# v1.net
KiCad netlist of a schematic drawn in EAGLE
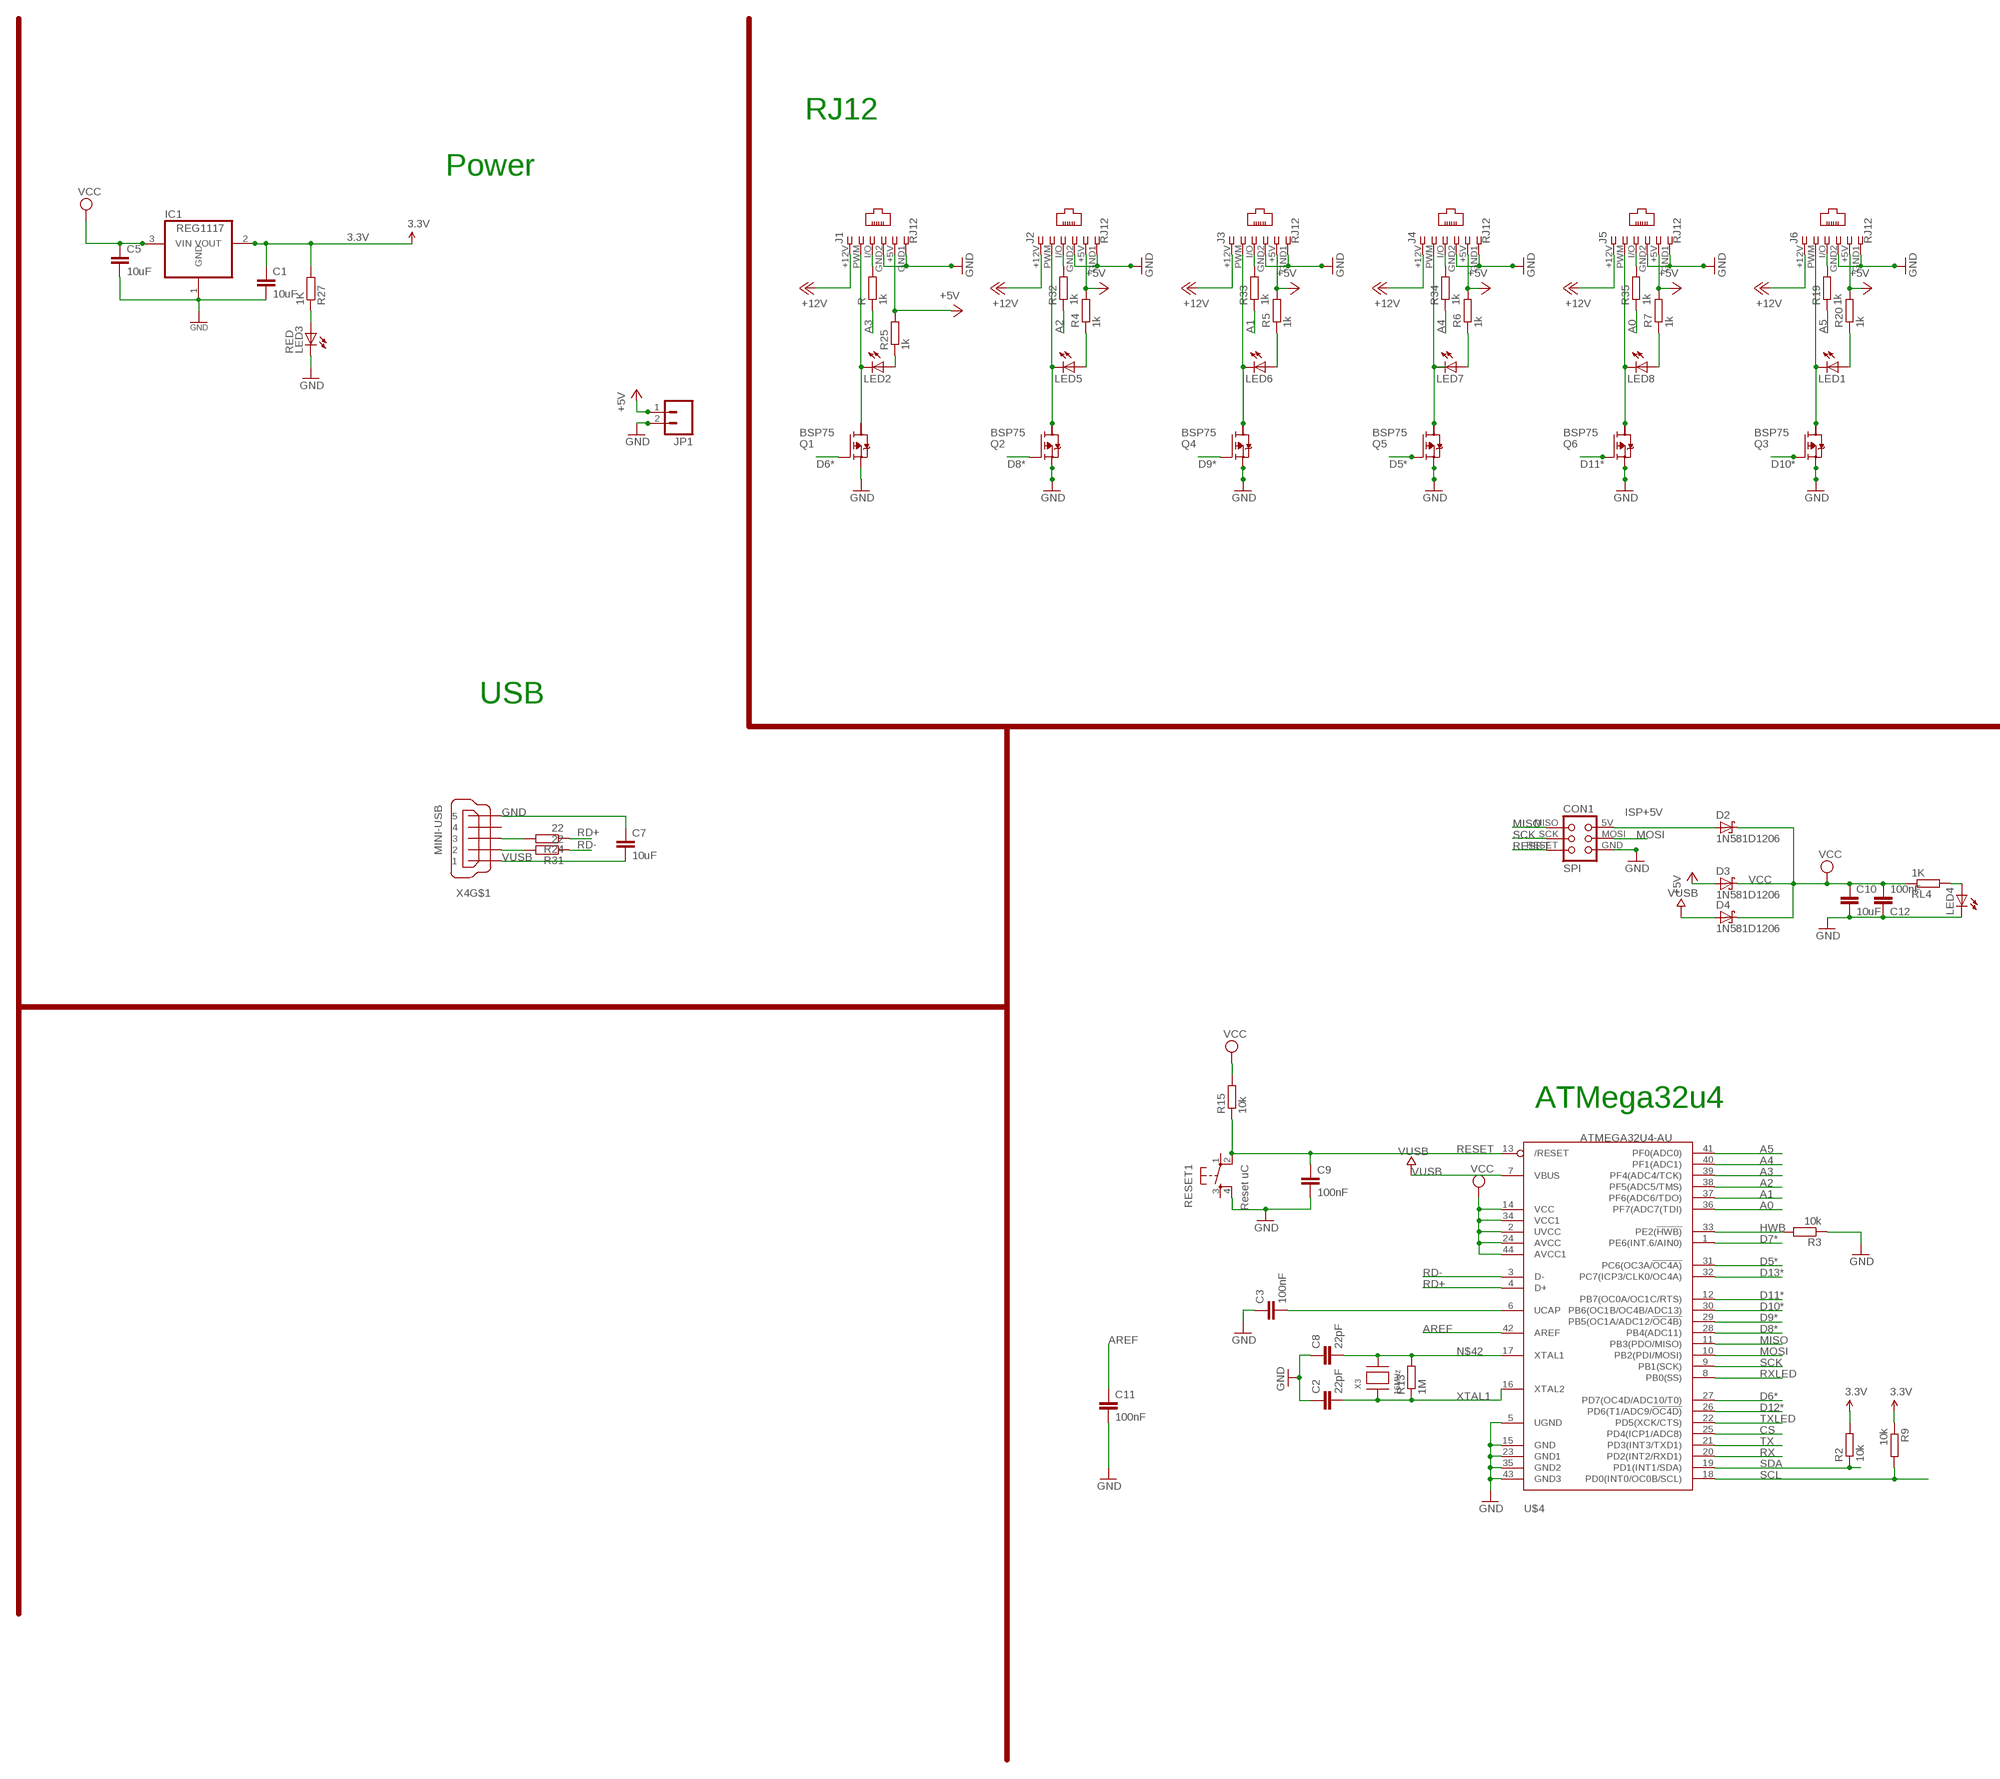
[diagram p0: schematic, sheet 1, part 1 of 2]
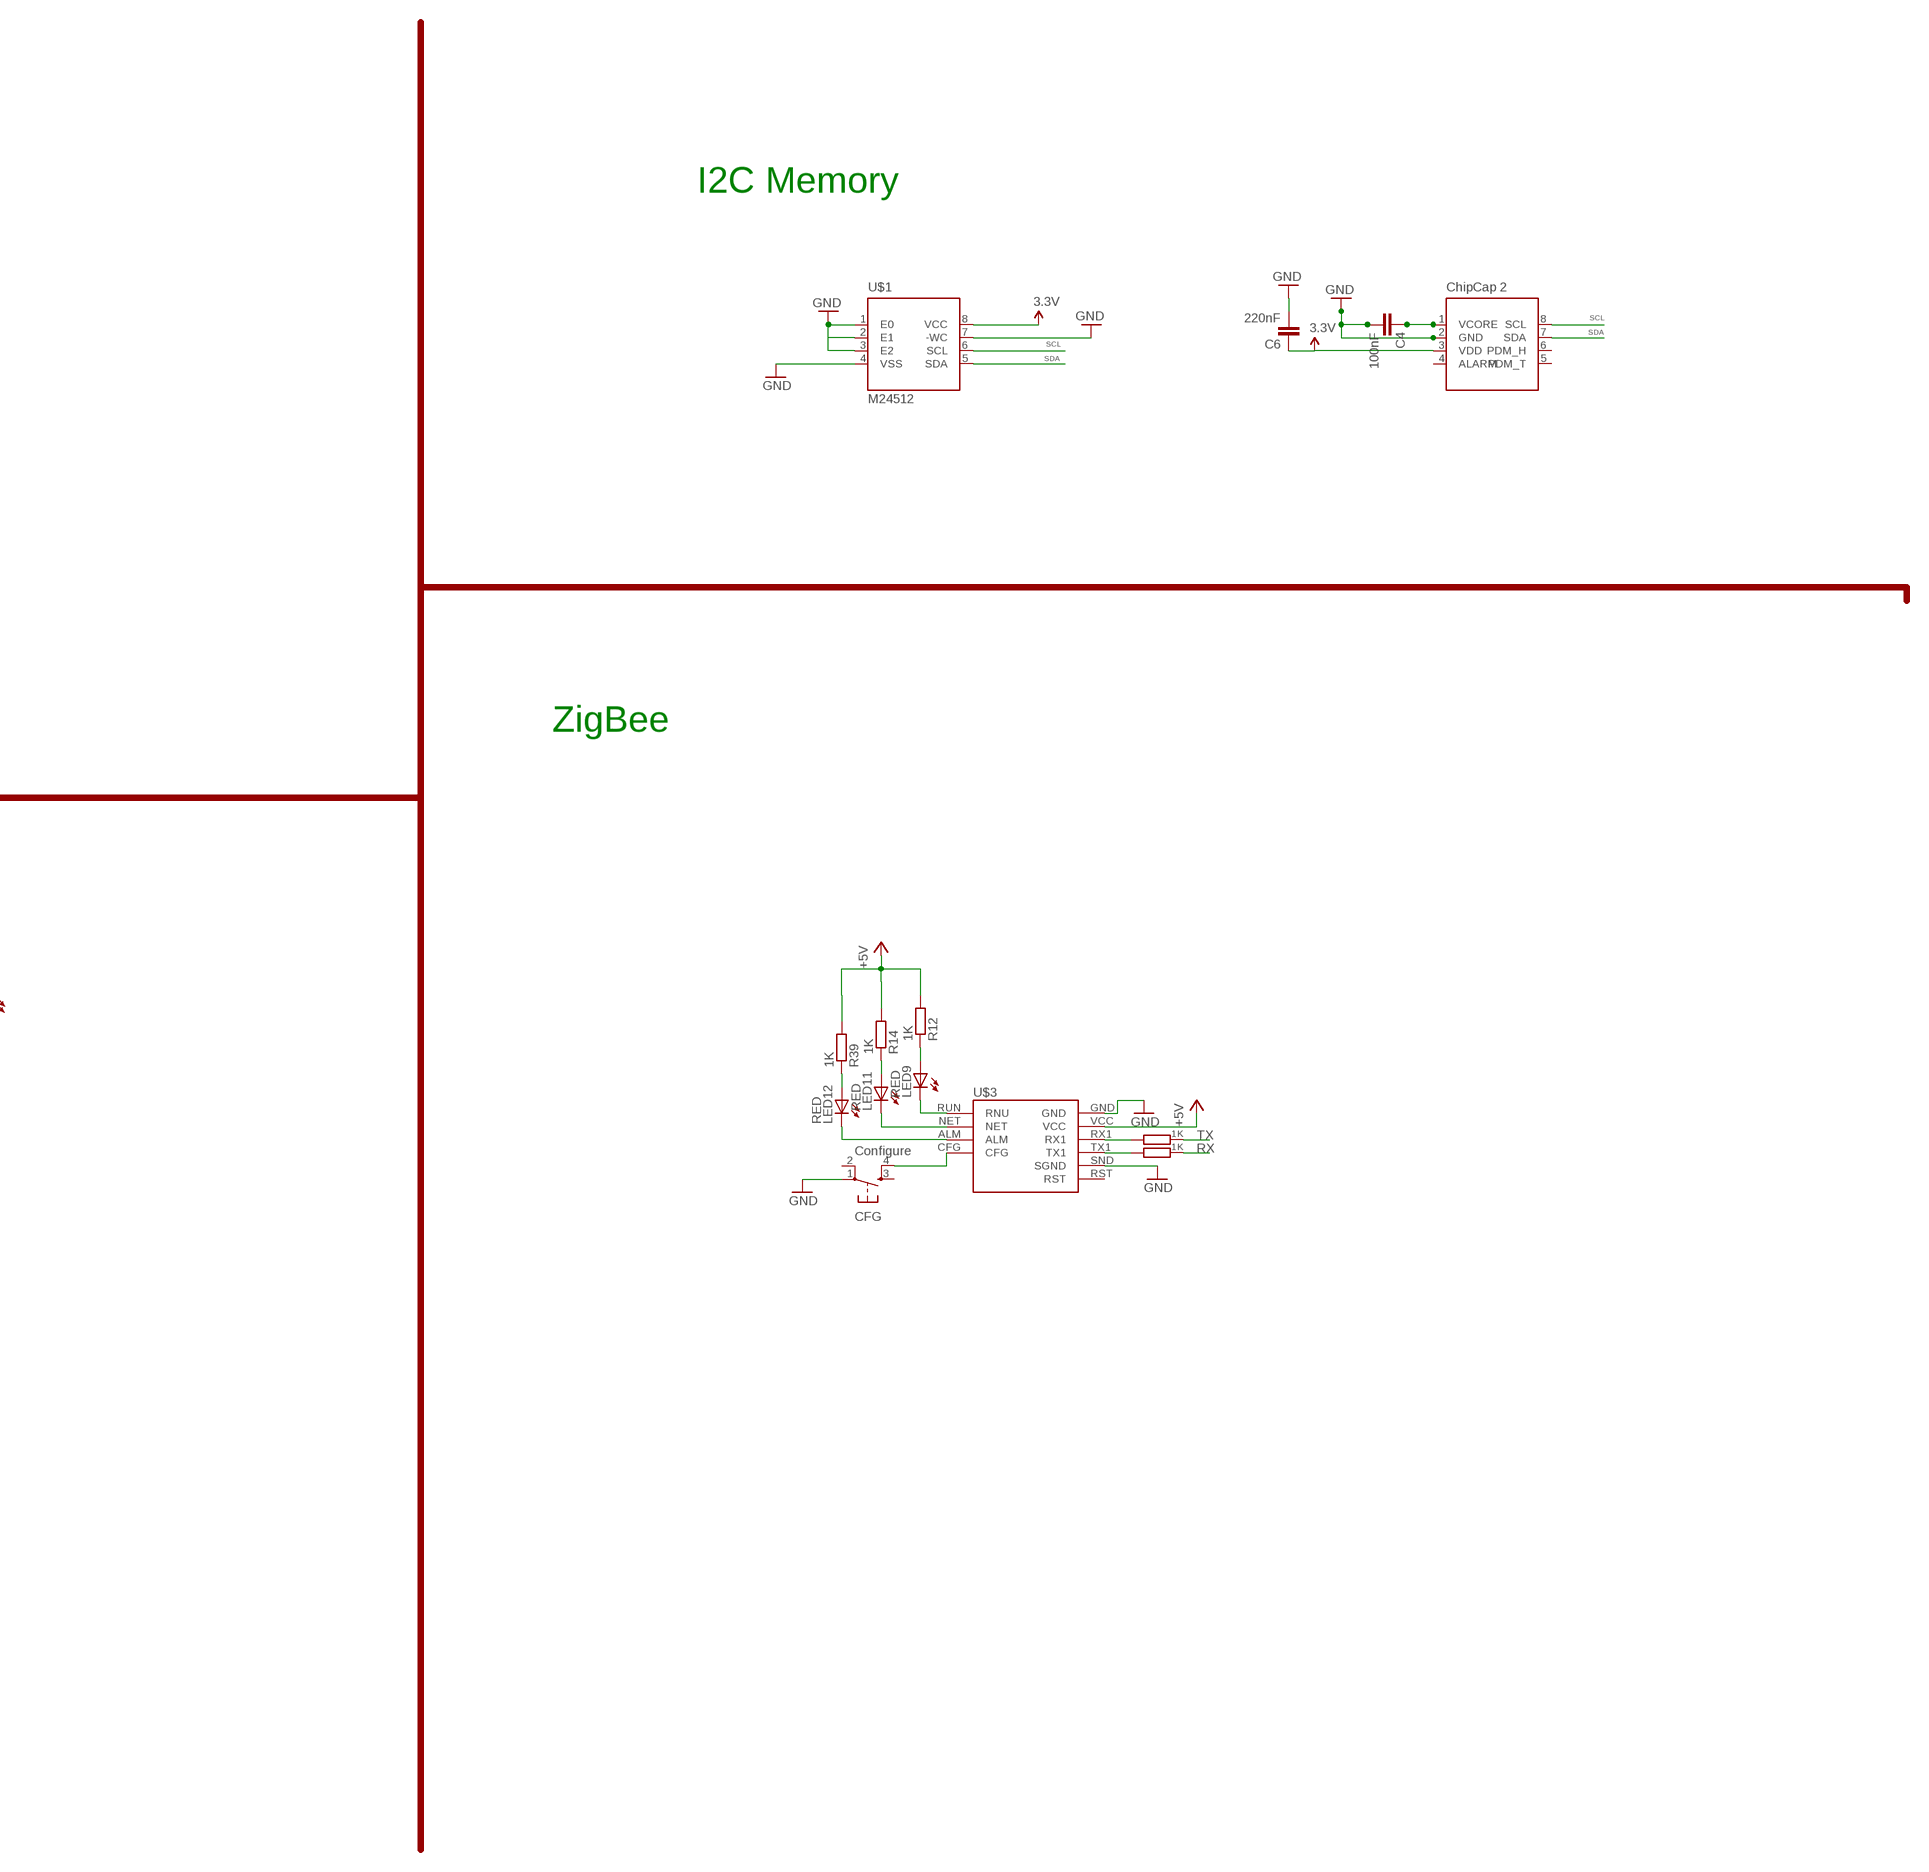
[diagram p1: schematic, sheet 1, part 2 of 2]

(export (version "E")
  (design (tool "Eeschema 10.0.6"))
  (components
    (comp (ref "C1")
      (value "10uF")
      (footprint "eagle-import:C1206")
      (libsource (lib "eagle-import") (part "C-EUC1206"))
    )
    (comp (ref "C2")
      (value "22pF")
      (footprint "eagle-import:C1206")
      (libsource (lib "eagle-import") (part "C-EUC1206"))
    )
    (comp (ref "C3")
      (value "100nF")
      (footprint "eagle-import:C1206")
      (libsource (lib "eagle-import") (part "C-EUC1206"))
    )
    (comp (ref "C4")
      (value "100nF")
      (footprint "eagle-import:C1206")
      (libsource (lib "eagle-import") (part "C-EUC1206"))
    )
    (comp (ref "C5")
      (value "10uF")
      (footprint "eagle-import:C1206")
      (libsource (lib "eagle-import") (part "C-EUC1206"))
    )
    (comp (ref "C6")
      (value "220nF")
      (footprint "eagle-import:C1206")
      (libsource (lib "eagle-import") (part "C-EUC1206"))
    )
    (comp (ref "C7")
      (value "10uF")
      (footprint "eagle-import:C1206")
      (libsource (lib "eagle-import") (part "C-EUC1206"))
    )
    (comp (ref "C8")
      (value "22pF")
      (footprint "eagle-import:C1206")
      (libsource (lib "eagle-import") (part "C-EUC1206"))
    )
    (comp (ref "C9")
      (value "100nF")
      (footprint "eagle-import:C1206")
      (libsource (lib "eagle-import") (part "C-EUC1206"))
    )
    (comp (ref "C10")
      (value "10uF")
      (footprint "eagle-import:C1206")
      (libsource (lib "eagle-import") (part "C-EUC1206"))
    )
    (comp (ref "C11")
      (value "100nF")
      (footprint "eagle-import:C1206")
      (libsource (lib "eagle-import") (part "C-EUC1206"))
    )
    (comp (ref "C12")
      (value "100nF")
      (footprint "eagle-import:C1206")
      (libsource (lib "eagle-import") (part "C-EUC1206"))
    )
    (comp (ref "CFG")
      (value "Configure")
      (footprint "eagle-import:TACTILE_SWITCH_SMD")
      (libsource (lib "eagle-import") (part "TAC_SWITCHSMD"))
    )
    (comp (ref "CON1")
      (value "SPI")
      (footprint "eagle-import:TC2030-MCP-NL")
      (libsource (lib "eagle-import") (part "TINYISPT"))
    )
    (comp (ref "D2")
      (value "1N581D1206")
      (footprint "eagle-import:LED-1206")
      (libsource (lib "eagle-import") (part "1N581D1206"))
    )
    (comp (ref "D3")
      (value "1N581D1206")
      (footprint "eagle-import:LED-1206")
      (libsource (lib "eagle-import") (part "1N581D1206"))
    )
    (comp (ref "D4")
      (value "1N581D1206")
      (footprint "eagle-import:LED-1206")
      (libsource (lib "eagle-import") (part "1N581D1206"))
    )
    (comp (ref "IC1")
      (value "REG1117")
      (footprint "eagle-import:SOT223")
      (libsource (lib "eagle-import") (part "REG1117"))
    )
    (comp (ref "J1")
      (value "RJ12")
      (footprint "eagle-import:RJ12-STRAIGHT")
      (libsource (lib "eagle-import") (part "RJ12STRAIGHT"))
    )
    (comp (ref "J2")
      (value "RJ12")
      (footprint "eagle-import:RJ12-STRAIGHT")
      (libsource (lib "eagle-import") (part "RJ12STRAIGHT"))
    )
    (comp (ref "J3")
      (value "RJ12")
      (footprint "eagle-import:RJ12-STRAIGHT")
      (libsource (lib "eagle-import") (part "RJ12STRAIGHT"))
    )
    (comp (ref "J4")
      (value "RJ12")
      (footprint "eagle-import:RJ12-STRAIGHT")
      (libsource (lib "eagle-import") (part "RJ12STRAIGHT"))
    )
    (comp (ref "J5")
      (value "RJ12")
      (footprint "eagle-import:RJ12-STRAIGHT")
      (libsource (lib "eagle-import") (part "RJ12STRAIGHT"))
    )
    (comp (ref "J6")
      (value "RJ12")
      (footprint "eagle-import:RJ12-STRAIGHT")
      (libsource (lib "eagle-import") (part "RJ12STRAIGHT"))
    )
    (comp (ref "JP1")
      (value "M02LOCK_LONGPADS")
      (footprint "eagle-import:1X02_LOCK_LONGPADS")
      (libsource (lib "eagle-import") (part "M02LOCK_LONGPADS"))
    )
    (comp (ref "LED1")
      (value "Blue")
      (footprint "eagle-import:LED3MM")
      (libsource (lib "eagle-import") (part "lpatiny_LED3MM"))
    )
    (comp (ref "LED2")
      (value "Blue")
      (footprint "eagle-import:LED3MM")
      (libsource (lib "eagle-import") (part "lpatiny_LED3MM"))
    )
    (comp (ref "LED3")
      (value "RED")
      (footprint "eagle-import:CHIP-LED0805")
      (libsource (lib "eagle-import") (part "LEDCHIP-LED0805"))
    )
    (comp (ref "LED4")
      (value "RED")
      (footprint "eagle-import:LED3MM")
      (libsource (lib "eagle-import") (part "lpatiny_LED3MM"))
    )
    (comp (ref "LED5")
      (value "Blue")
      (footprint "eagle-import:LED3MM")
      (libsource (lib "eagle-import") (part "lpatiny_LED3MM"))
    )
    (comp (ref "LED6")
      (value "Blue")
      (footprint "eagle-import:LED3MM")
      (libsource (lib "eagle-import") (part "lpatiny_LED3MM"))
    )
    (comp (ref "LED7")
      (value "BLue")
      (footprint "eagle-import:LED3MM")
      (libsource (lib "eagle-import") (part "lpatiny_LED3MM"))
    )
    (comp (ref "LED8")
      (value "Blue")
      (footprint "eagle-import:LED3MM")
      (libsource (lib "eagle-import") (part "lpatiny_LED3MM"))
    )
    (comp (ref "LED9")
      (value "RED")
      (footprint "eagle-import:CHIP-LED0805")
      (libsource (lib "eagle-import") (part "LEDCHIP-LED0805"))
    )
    (comp (ref "LED11")
      (value "RED")
      (footprint "eagle-import:CHIP-LED0805")
      (libsource (lib "eagle-import") (part "LEDCHIP-LED0805"))
    )
    (comp (ref "LED12")
      (value "RED")
      (footprint "eagle-import:CHIP-LED0805")
      (libsource (lib "eagle-import") (part "LEDCHIP-LED0805"))
    )
    (comp (ref "Q1")
      (value "BSP75")
      (footprint "eagle-import:PG-SOT-223")
      (libsource (lib "eagle-import") (part "BSP613P"))
    )
    (comp (ref "Q2")
      (value "BSP75")
      (footprint "eagle-import:PG-SOT-223")
      (libsource (lib "eagle-import") (part "BSP613P"))
    )
    (comp (ref "Q3")
      (value "BSP75")
      (footprint "eagle-import:PG-SOT-223")
      (libsource (lib "eagle-import") (part "BSP613P"))
    )
    (comp (ref "Q4")
      (value "BSP75")
      (footprint "eagle-import:PG-SOT-223")
      (libsource (lib "eagle-import") (part "BSP613P"))
    )
    (comp (ref "Q5")
      (value "BSP75")
      (footprint "eagle-import:PG-SOT-223")
      (libsource (lib "eagle-import") (part "BSP613P"))
    )
    (comp (ref "Q6")
      (value "BSP75")
      (footprint "eagle-import:PG-SOT-223")
      (libsource (lib "eagle-import") (part "BSP613P"))
    )
    (comp (ref "R")
      (value "1k")
      (footprint "eagle-import:R0805")
      (libsource (lib "eagle-import") (part "R-EU_R0805"))
    )
    (comp (ref "R2")
      (value "10k")
      (footprint "eagle-import:M1206")
      (libsource (lib "eagle-import") (part "resistor_R-EU_M1206"))
    )
    (comp (ref "R3")
      (value "10k")
      (footprint "eagle-import:M0805")
      (libsource (lib "eagle-import") (part "resistor_R-EU_M0805"))
    )
    (comp (ref "R4")
      (value "1k")
      (footprint "eagle-import:R0805")
      (libsource (lib "eagle-import") (part "R-EU_R0805"))
    )
    (comp (ref "R5")
      (value "1k")
      (footprint "eagle-import:R0805")
      (libsource (lib "eagle-import") (part "R-EU_R0805"))
    )
    (comp (ref "R6")
      (value "1k")
      (footprint "eagle-import:R0805")
      (libsource (lib "eagle-import") (part "R-EU_R0805"))
    )
    (comp (ref "R7")
      (value "1k")
      (footprint "eagle-import:R0805")
      (libsource (lib "eagle-import") (part "R-EU_R0805"))
    )
    (comp (ref "R8")
      (value "1K")
      (footprint "eagle-import:R0805")
      (libsource (lib "eagle-import") (part "R-EU_R0805"))
    )
    (comp (ref "R9")
      (value "10k")
      (footprint "eagle-import:M1206")
      (libsource (lib "eagle-import") (part "resistor_R-EU_M1206"))
    )
    (comp (ref "R11")
      (value "1K")
      (footprint "eagle-import:R0805")
      (libsource (lib "eagle-import") (part "R-EU_R0805"))
    )
    (comp (ref "R12")
      (value "1K")
      (footprint "eagle-import:R0805")
      (libsource (lib "eagle-import") (part "R-EU_R0805"))
    )
    (comp (ref "R13")
      (value "1M")
      (footprint "eagle-import:R1206")
      (libsource (lib "eagle-import") (part "R-EU_R1206"))
    )
    (comp (ref "R14")
      (value "1K")
      (footprint "eagle-import:R0805")
      (libsource (lib "eagle-import") (part "R-EU_R0805"))
    )
    (comp (ref "R15")
      (value "10k")
      (footprint "eagle-import:M0805")
      (libsource (lib "eagle-import") (part "resistor_R-EU_M0805"))
    )
    (comp (ref "R19")
      (value "1k")
      (footprint "eagle-import:R0805")
      (libsource (lib "eagle-import") (part "R-EU_R0805"))
    )
    (comp (ref "R20")
      (value "1k")
      (footprint "eagle-import:R0805")
      (libsource (lib "eagle-import") (part "R-EU_R0805"))
    )
    (comp (ref "R24")
      (value "22")
      (footprint "eagle-import:M1206")
      (libsource (lib "eagle-import") (part "resistor_R-EU_M1206"))
    )
    (comp (ref "R25")
      (value "1k")
      (footprint "eagle-import:R0805")
      (libsource (lib "eagle-import") (part "R-EU_R0805"))
    )
    (comp (ref "R27")
      (value "1K")
      (footprint "eagle-import:R0805")
      (libsource (lib "eagle-import") (part "R-EU_R0805"))
    )
    (comp (ref "R31")
      (value "22")
      (footprint "eagle-import:M1206")
      (libsource (lib "eagle-import") (part "resistor_R-EU_M1206"))
    )
    (comp (ref "R32")
      (value "1k")
      (footprint "eagle-import:R0805")
      (libsource (lib "eagle-import") (part "R-EU_R0805"))
    )
    (comp (ref "R33")
      (value "1k")
      (footprint "eagle-import:R0805")
      (libsource (lib "eagle-import") (part "R-EU_R0805"))
    )
    (comp (ref "R34")
      (value "1k")
      (footprint "eagle-import:R0805")
      (libsource (lib "eagle-import") (part "R-EU_R0805"))
    )
    (comp (ref "R35")
      (value "1k")
      (footprint "eagle-import:R0805")
      (libsource (lib "eagle-import") (part "R-EU_R0805"))
    )
    (comp (ref "R39")
      (value "1K")
      (footprint "eagle-import:R0805")
      (libsource (lib "eagle-import") (part "R-EU_R0805"))
    )
    (comp (ref "RESET1")
      (value "Reset uC")
      (footprint "eagle-import:TACTILE_SWITCH_SMD")
      (libsource (lib "eagle-import") (part "TAC_SWITCHSMD"))
    )
    (comp (ref "RL4")
      (value "1K")
      (footprint "eagle-import:R0805")
      (libsource (lib "eagle-import") (part "resistor_R-EU_R0805"))
    )
    (comp (ref "U$1")
      (value "M24512")
      (footprint "eagle-import:SO8")
      (libsource (lib "eagle-import") (part "M24512"))
    )
    (comp (ref "U$2")
      (value "CHIPCAP")
      (footprint "eagle-import:CHIPCAP")
      (libsource (lib "eagle-import") (part "CHIPCAP"))
    )
    (comp (ref "U$3")
      (value "SZ05-ZIGBEESMD")
      (footprint "eagle-import:SZ05-ZIGBEE3")
      (libsource (lib "eagle-import") (part "SZ05-ZIGBEESMD"))
    )
    (comp (ref "U$4")
      (value "ATMEGA32U4-AU")
      (footprint "eagle-import:TQFP44")
      (libsource (lib "eagle-import") (part "ATMEGA32U4-AU"))
    )
    (comp (ref "X3")
      (value "16MHz")
      (footprint "eagle-import:NX6035")
      (libsource (lib "eagle-import") (part "XTALNX6035"))
    )
    (comp (ref "X4")
      (value "MINI-USB")
      (footprint "eagle-import:32005-201")
      (libsource (lib "eagle-import") (part "MINI-USB-SCHIELD-32005-201"))
    )
  )
  (nets
    (net (code "1") (name "+5V") (class "Default")
      (node (ref "D3") (pin "A") (pinfunction "A_A") (pintype "passive"))
      (node (ref "J1") (pin "+5V") (pinfunction "5_+5V") (pintype "bidirectional"))
      (node (ref "J2") (pin "+5V") (pinfunction "5_+5V") (pintype "bidirectional"))
      (node (ref "J3") (pin "+5V") (pinfunction "5_+5V") (pintype "bidirectional"))
      (node (ref "J4") (pin "+5V") (pinfunction "5_+5V") (pintype "bidirectional"))
      (node (ref "J5") (pin "+5V") (pinfunction "5_+5V") (pintype "bidirectional"))
      (node (ref "J6") (pin "+5V") (pinfunction "5_+5V") (pintype "bidirectional"))
      (node (ref "JP1") (pin "1") (pinfunction "1_1") (pintype "passive"))
      (node (ref "R12") (pin "2") (pinfunction "2_2") (pintype "passive"))
      (node (ref "R14") (pin "2") (pinfunction "2_2") (pintype "passive"))
      (node (ref "R20") (pin "2") (pinfunction "2_2") (pintype "passive"))
      (node (ref "R25") (pin "2") (pinfunction "2_2") (pintype "passive"))
      (node (ref "R39") (pin "2") (pinfunction "2_2") (pintype "passive"))
      (node (ref "R4") (pin "2") (pinfunction "2_2") (pintype "passive"))
      (node (ref "R5") (pin "2") (pinfunction "2_2") (pintype "passive"))
      (node (ref "R6") (pin "2") (pinfunction "2_2") (pintype "passive"))
      (node (ref "R7") (pin "2") (pinfunction "2_2") (pintype "passive"))
      (node (ref "U$3") (pin "VCC") (pinfunction "VCC_VCC") (pintype "bidirectional"))
    )
    (net (code "2") (name "+12V") (class "Default")
      (node (ref "J1") (pin "+12V") (pinfunction "1_+12V") (pintype "bidirectional"))
      (node (ref "J2") (pin "+12V") (pinfunction "1_+12V") (pintype "bidirectional"))
      (node (ref "J3") (pin "+12V") (pinfunction "1_+12V") (pintype "bidirectional"))
      (node (ref "J4") (pin "+12V") (pinfunction "1_+12V") (pintype "bidirectional"))
      (node (ref "J5") (pin "+12V") (pinfunction "1_+12V") (pintype "bidirectional"))
      (node (ref "J6") (pin "+12V") (pinfunction "1_+12V") (pintype "bidirectional"))
    )
    (net (code "3") (name "/A0") (class "Default")
      (node (ref "R35") (pin "1") (pinfunction "1_1") (pintype "passive"))
      (node (ref "U$4") (pin "36") (pinfunction "PF7(ADC7(TDI)_36") (pintype "bidirectional"))
    )
    (net (code "4") (name "/A1") (class "Default")
      (node (ref "R33") (pin "1") (pinfunction "1_1") (pintype "passive"))
      (node (ref "U$4") (pin "37") (pinfunction "PF6(ADC6/TDO)_37") (pintype "bidirectional"))
    )
    (net (code "5") (name "/A2") (class "Default")
      (node (ref "R32") (pin "1") (pinfunction "1_1") (pintype "passive"))
      (node (ref "U$4") (pin "38") (pinfunction "PF5(ADC5/TMS)_38") (pintype "bidirectional"))
    )
    (net (code "6") (name "/A3") (class "Default")
      (node (ref "R") (pin "1") (pinfunction "1_1") (pintype "passive"))
      (node (ref "U$4") (pin "39") (pinfunction "PF4(ADC4/TCK)_39") (pintype "bidirectional"))
    )
    (net (code "7") (name "/A4") (class "Default")
      (node (ref "R34") (pin "1") (pinfunction "1_1") (pintype "passive"))
      (node (ref "U$4") (pin "40") (pinfunction "PF1(ADC1)_40") (pintype "bidirectional"))
    )
    (net (code "8") (name "/A5") (class "Default")
      (node (ref "R19") (pin "1") (pinfunction "1_1") (pintype "passive"))
      (node (ref "U$4") (pin "41") (pinfunction "PF0(ADC0)_41") (pintype "bidirectional"))
    )
    (net (code "9") (name "/AREF") (class "Default")
      (node (ref "C11") (pin "1") (pinfunction "1_1") (pintype "passive"))
      (node (ref "U$4") (pin "42") (pinfunction "AREF_42") (pintype "bidirectional"))
    )
    (net (code "10") (name "/CS") (class "Default")
      (node (ref "U$4") (pin "25") (pinfunction "PD4(ICP1/ADC8)_25") (pintype "bidirectional"))
    )
    (net (code "11") (name "/D5*") (class "Default")
      (node (ref "Q5") (pin "1") (pinfunction "G_1") (pintype "passive"))
      (node (ref "U$4") (pin "31") (pinfunction "PC6(OC3A/~{OC4A})_31") (pintype "bidirectional"))
    )
    (net (code "12") (name "/D6*") (class "Default")
      (node (ref "Q1") (pin "1") (pinfunction "G_1") (pintype "passive"))
      (node (ref "U$4") (pin "27") (pinfunction "PD7(OC4D/ADC10/T0)_27") (pintype "bidirectional"))
    )
    (net (code "13") (name "/D7*") (class "Default")
      (node (ref "U$4") (pin "1") (pinfunction "PE6(INT.6/AIN0)_1") (pintype "bidirectional"))
    )
    (net (code "14") (name "/D8*") (class "Default")
      (node (ref "Q2") (pin "1") (pinfunction "G_1") (pintype "passive"))
      (node (ref "U$4") (pin "28") (pinfunction "PB4(ADC11)_28") (pintype "bidirectional"))
    )
    (net (code "15") (name "/D9*") (class "Default")
      (node (ref "Q4") (pin "1") (pinfunction "G_1") (pintype "passive"))
      (node (ref "U$4") (pin "29") (pinfunction "PB5(OC1A/ADC12/~{OC4B})_29") (pintype "bidirectional"))
    )
    (net (code "16") (name "/D10*") (class "Default")
      (node (ref "Q3") (pin "1") (pinfunction "G_1") (pintype "passive"))
      (node (ref "U$4") (pin "30") (pinfunction "PB6(OC1B/OC4B/ADC13)_30") (pintype "bidirectional"))
    )
    (net (code "17") (name "/D11*") (class "Default")
      (node (ref "Q6") (pin "1") (pinfunction "G_1") (pintype "passive"))
      (node (ref "U$4") (pin "12") (pinfunction "PB7(OC0A/OC1C/RTS)_12") (pintype "bidirectional"))
    )
    (net (code "18") (name "/D12*") (class "Default")
      (node (ref "U$4") (pin "26") (pinfunction "PD6(T1/ADC9/~{OC4D})_26") (pintype "bidirectional"))
    )
    (net (code "19") (name "/D13*") (class "Default")
      (node (ref "U$4") (pin "32") (pinfunction "PC7(ICP3/CLK0/OC4A)_32") (pintype "bidirectional"))
    )
    (net (code "20") (name "/HWB") (class "Default")
      (node (ref "R3") (pin "2") (pinfunction "2_2") (pintype "passive"))
      (node (ref "U$4") (pin "33") (pinfunction "PE2(~{HWB})_33") (pintype "bidirectional"))
    )
    (net (code "21") (name "/ISP+5V") (class "Default")
      (node (ref "CON1") (pin "5V") (pinfunction "VCC_5V") (pintype "passive"))
      (node (ref "D2") (pin "A") (pinfunction "A_A") (pintype "passive"))
    )
    (net (code "22") (name "/MISO") (class "Default")
      (node (ref "CON1") (pin "MISO") (pinfunction "MISO_MISO") (pintype "passive"))
      (node (ref "U$4") (pin "11") (pinfunction "PB3(PDO/MISO)_11") (pintype "bidirectional"))
    )
    (net (code "23") (name "/MOSI") (class "Default")
      (node (ref "CON1") (pin "MOSI") (pinfunction "MOSI_MOSI") (pintype "passive"))
      (node (ref "U$4") (pin "10") (pinfunction "PB2(PDI/MOSI)_10") (pintype "bidirectional"))
    )
    (net (code "24") (name "/N$42") (class "Default")
      (node (ref "C8") (pin "2") (pinfunction "2_2") (pintype "passive"))
      (node (ref "R13") (pin "2") (pinfunction "2_2") (pintype "passive"))
      (node (ref "U$4") (pin "17") (pinfunction "XTAL1_17") (pintype "bidirectional"))
      (node (ref "X3") (pin "P$2") (pinfunction "P$2_P$2") (pintype "bidirectional"))
    )
    (net (code "25") (name "/RD+") (class "Default")
      (node (ref "R24") (pin "1") (pinfunction "1_1") (pintype "passive"))
      (node (ref "U$4") (pin "4") (pinfunction "D+_4") (pintype "bidirectional"))
    )
    (net (code "26") (name "/RD-") (class "Default")
      (node (ref "R31") (pin "1") (pinfunction "1_1") (pintype "passive"))
      (node (ref "U$4") (pin "3") (pinfunction "D-_3") (pintype "bidirectional"))
    )
    (net (code "27") (name "/RESET") (class "Default")
      (node (ref "C9") (pin "1") (pinfunction "1_1") (pintype "passive"))
      (node (ref "CON1") (pin "RESET") (pinfunction "RESET_RESET") (pintype "passive"))
      (node (ref "R15") (pin "1") (pinfunction "1_1") (pintype "passive"))
      (node (ref "RESET1") (pin "2") (pinfunction "2_2") (pintype "passive"))
      (node (ref "U$4") (pin "13") (pinfunction "/RESET_13") (pintype "bidirectional"))
    )
    (net (code "28") (name "/RX") (class "Default")
      (node (ref "R8") (pin "1") (pinfunction "1_1") (pintype "passive"))
      (node (ref "U$4") (pin "20") (pinfunction "PD2(INT2/RXD1)_20") (pintype "bidirectional"))
    )
    (net (code "29") (name "/RXLED") (class "Default")
      (node (ref "U$4") (pin "8") (pinfunction "PB0(SS)_8") (pintype "bidirectional"))
    )
    (net (code "30") (name "/SCK") (class "Default")
      (node (ref "CON1") (pin "SCK") (pinfunction "SCK_SCK") (pintype "passive"))
      (node (ref "U$4") (pin "9") (pinfunction "PB1(SCK)_9") (pintype "bidirectional"))
    )
    (net (code "31") (name "/SCL") (class "Default")
      (node (ref "R9") (pin "2") (pinfunction "2_2") (pintype "passive"))
      (node (ref "U$1") (pin "6") (pinfunction "SCL_6") (pintype "bidirectional"))
      (node (ref "U$2") (pin "8") (pinfunction "SCL_8") (pintype "bidirectional"))
      (node (ref "U$4") (pin "18") (pinfunction "PD0(INT0/OC0B/SCL)_18") (pintype "bidirectional"))
    )
    (net (code "32") (name "/SDA") (class "Default")
      (node (ref "R2") (pin "1") (pinfunction "1_1") (pintype "passive"))
      (node (ref "U$1") (pin "5") (pinfunction "SDA_5") (pintype "bidirectional"))
      (node (ref "U$2") (pin "7") (pinfunction "SDA_7") (pintype "bidirectional"))
      (node (ref "U$4") (pin "19") (pinfunction "PD1(INT1/SDA)_19") (pintype "bidirectional"))
    )
    (net (code "33") (name "/TX") (class "Default")
      (node (ref "R11") (pin "1") (pinfunction "1_1") (pintype "passive"))
      (node (ref "U$4") (pin "21") (pinfunction "PD3(INT3/TXD1)_21") (pintype "bidirectional"))
    )
    (net (code "34") (name "/TXLED") (class "Default")
      (node (ref "U$4") (pin "22") (pinfunction "PD5(XCK/CTS)_22") (pintype "bidirectional"))
    )
    (net (code "35") (name "/XTAL1") (class "Default")
      (node (ref "C2") (pin "2") (pinfunction "2_2") (pintype "passive"))
      (node (ref "R13") (pin "1") (pinfunction "1_1") (pintype "passive"))
      (node (ref "U$4") (pin "16") (pinfunction "XTAL2_16") (pintype "bidirectional"))
      (node (ref "X3") (pin "P$1") (pinfunction "P$1_P$1") (pintype "bidirectional"))
    )
    (net (code "36") (name "3.3V") (class "Default")
      (node (ref "C1") (pin "1") (pinfunction "1_1") (pintype "passive"))
      (node (ref "C6") (pin "1") (pinfunction "1_1") (pintype "passive"))
      (node (ref "IC1") (pin "2") (pinfunction "VOUT_2") (pintype "output"))
      (node (ref "R2") (pin "2") (pinfunction "2_2") (pintype "passive"))
      (node (ref "R27") (pin "2") (pinfunction "2_2") (pintype "passive"))
      (node (ref "R9") (pin "1") (pinfunction "1_1") (pintype "passive"))
      (node (ref "U$1") (pin "8") (pinfunction "VCC_8") (pintype "power_in"))
      (node (ref "U$2") (pin "3") (pinfunction "VDD_3") (pintype "power_in"))
    )
    (net (code "37") (name "GND") (class "Default")
      (node (ref "C1") (pin "2") (pinfunction "2_2") (pintype "passive"))
      (node (ref "C10") (pin "2") (pinfunction "2_2") (pintype "passive"))
      (node (ref "C11") (pin "2") (pinfunction "2_2") (pintype "passive"))
      (node (ref "C12") (pin "1") (pinfunction "1_1") (pintype "passive"))
      (node (ref "C2") (pin "1") (pinfunction "1_1") (pintype "passive"))
      (node (ref "C3") (pin "1") (pinfunction "1_1") (pintype "passive"))
      (node (ref "C4") (pin "2") (pinfunction "2_2") (pintype "passive"))
      (node (ref "C5") (pin "2") (pinfunction "2_2") (pintype "passive"))
      (node (ref "C6") (pin "2") (pinfunction "2_2") (pintype "passive"))
      (node (ref "C7") (pin "1") (pinfunction "1_1") (pintype "passive"))
      (node (ref "C8") (pin "1") (pinfunction "1_1") (pintype "passive"))
      (node (ref "C9") (pin "2") (pinfunction "2_2") (pintype "passive"))
      (node (ref "CFG") (pin "1") (pinfunction "1_1") (pintype "passive"))
      (node (ref "CON1") (pin "GND") (pinfunction "GND_GND") (pintype "passive"))
      (node (ref "IC1") (pin "1") (pinfunction "GND_1") (pintype "power_in"))
      (node (ref "J1") (pin "GND1") (pinfunction "6_GND1") (pintype "bidirectional"))
      (node (ref "J1") (pin "GND2") (pinfunction "4_GND2") (pintype "bidirectional"))
      (node (ref "J2") (pin "GND1") (pinfunction "6_GND1") (pintype "bidirectional"))
      (node (ref "J2") (pin "GND2") (pinfunction "4_GND2") (pintype "bidirectional"))
      (node (ref "J3") (pin "GND1") (pinfunction "6_GND1") (pintype "bidirectional"))
      (node (ref "J3") (pin "GND2") (pinfunction "4_GND2") (pintype "bidirectional"))
      (node (ref "J4") (pin "GND1") (pinfunction "6_GND1") (pintype "bidirectional"))
      (node (ref "J4") (pin "GND2") (pinfunction "4_GND2") (pintype "bidirectional"))
      (node (ref "J5") (pin "GND1") (pinfunction "6_GND1") (pintype "bidirectional"))
      (node (ref "J5") (pin "GND2") (pinfunction "4_GND2") (pintype "bidirectional"))
      (node (ref "J6") (pin "GND1") (pinfunction "6_GND1") (pintype "bidirectional"))
      (node (ref "J6") (pin "GND2") (pinfunction "4_GND2") (pintype "bidirectional"))
      (node (ref "JP1") (pin "2") (pinfunction "2_2") (pintype "passive"))
      (node (ref "LED3") (pin "C") (pinfunction "C_C") (pintype "passive"))
      (node (ref "LED4") (pin "K") (pinfunction "C_K") (pintype "passive"))
      (node (ref "Q1") (pin "3") (pinfunction "S_3") (pintype "passive"))
      (node (ref "Q2") (pin "3") (pinfunction "S_3") (pintype "passive"))
      (node (ref "Q3") (pin "3") (pinfunction "S_3") (pintype "passive"))
      (node (ref "Q4") (pin "3") (pinfunction "S_3") (pintype "passive"))
      (node (ref "Q5") (pin "3") (pinfunction "S_3") (pintype "passive"))
      (node (ref "Q6") (pin "3") (pinfunction "S_3") (pintype "passive"))
      (node (ref "R3") (pin "1") (pinfunction "1_1") (pintype "passive"))
      (node (ref "RESET1") (pin "4") (pinfunction "4_4") (pintype "passive"))
      (node (ref "U$1") (pin "1") (pinfunction "E0_1") (pintype "bidirectional"))
      (node (ref "U$1") (pin "2") (pinfunction "E1_2") (pintype "bidirectional"))
      (node (ref "U$1") (pin "3") (pinfunction "E2_3") (pintype "bidirectional"))
      (node (ref "U$1") (pin "4") (pinfunction "VSS_4") (pintype "power_in"))
      (node (ref "U$1") (pin "7") (pinfunction "-WC_7") (pintype "bidirectional"))
      (node (ref "U$2") (pin "2") (pinfunction "GND_2") (pintype "power_in"))
      (node (ref "U$3") (pin "GND") (pinfunction "GND_GND") (pintype "bidirectional"))
      (node (ref "U$3") (pin "SND") (pinfunction "SGND_SND") (pintype "bidirectional"))
      (node (ref "U$4") (pin "15") (pinfunction "GND_15") (pintype "bidirectional"))
      (node (ref "U$4") (pin "23") (pinfunction "GND1_23") (pintype "bidirectional"))
      (node (ref "U$4") (pin "35") (pinfunction "GND2_35") (pintype "bidirectional"))
      (node (ref "U$4") (pin "43") (pinfunction "GND3_43") (pintype "bidirectional"))
      (node (ref "U$4") (pin "5") (pinfunction "UGND_5") (pintype "bidirectional"))
      (node (ref "X4") (pin "5") (pinfunction "5_5") (pintype "passive"))
    )
    (net (code "38") (name "Net-(CFG-Pad4)") (class "Default")
      (node (ref "CFG") (pin "4") (pinfunction "4_4") (pintype "passive"))
      (node (ref "U$3") (pin "CFG") (pinfunction "CFG_CFG") (pintype "bidirectional"))
    )
    (net (code "39") (name "Net-(J1-2)") (class "Default")
      (node (ref "J1") (pin "PWM") (pinfunction "2_PWM") (pintype "bidirectional"))
      (node (ref "LED2") (pin "K") (pinfunction "C_K") (pintype "passive"))
      (node (ref "Q1") (pin "2") (pinfunction "D_2") (pintype "passive"))
    )
    (net (code "40") (name "Net-(J1-3)") (class "Default")
      (node (ref "J1") (pin "I/O") (pinfunction "3_I/O") (pintype "bidirectional"))
      (node (ref "R") (pin "2") (pinfunction "2_2") (pintype "passive"))
    )
    (net (code "41") (name "Net-(J2-2)") (class "Default")
      (node (ref "J2") (pin "PWM") (pinfunction "2_PWM") (pintype "bidirectional"))
      (node (ref "LED5") (pin "K") (pinfunction "C_K") (pintype "passive"))
      (node (ref "Q2") (pin "2") (pinfunction "D_2") (pintype "passive"))
    )
    (net (code "42") (name "Net-(J2-3)") (class "Default")
      (node (ref "J2") (pin "I/O") (pinfunction "3_I/O") (pintype "bidirectional"))
      (node (ref "R32") (pin "2") (pinfunction "2_2") (pintype "passive"))
    )
    (net (code "43") (name "Net-(J3-2)") (class "Default")
      (node (ref "J3") (pin "PWM") (pinfunction "2_PWM") (pintype "bidirectional"))
      (node (ref "LED6") (pin "K") (pinfunction "C_K") (pintype "passive"))
      (node (ref "Q4") (pin "2") (pinfunction "D_2") (pintype "passive"))
    )
    (net (code "44") (name "Net-(J3-3)") (class "Default")
      (node (ref "J3") (pin "I/O") (pinfunction "3_I/O") (pintype "bidirectional"))
      (node (ref "R33") (pin "2") (pinfunction "2_2") (pintype "passive"))
    )
    (net (code "45") (name "Net-(J4-2)") (class "Default")
      (node (ref "J4") (pin "PWM") (pinfunction "2_PWM") (pintype "bidirectional"))
      (node (ref "LED7") (pin "K") (pinfunction "C_K") (pintype "passive"))
      (node (ref "Q5") (pin "2") (pinfunction "D_2") (pintype "passive"))
    )
    (net (code "46") (name "Net-(J4-3)") (class "Default")
      (node (ref "J4") (pin "I/O") (pinfunction "3_I/O") (pintype "bidirectional"))
      (node (ref "R34") (pin "2") (pinfunction "2_2") (pintype "passive"))
    )
    (net (code "47") (name "Net-(J5-2)") (class "Default")
      (node (ref "J5") (pin "PWM") (pinfunction "2_PWM") (pintype "bidirectional"))
      (node (ref "LED8") (pin "K") (pinfunction "C_K") (pintype "passive"))
      (node (ref "Q6") (pin "2") (pinfunction "D_2") (pintype "passive"))
    )
    (net (code "48") (name "Net-(J5-3)") (class "Default")
      (node (ref "J5") (pin "I/O") (pinfunction "3_I/O") (pintype "bidirectional"))
      (node (ref "R35") (pin "2") (pinfunction "2_2") (pintype "passive"))
    )
    (net (code "49") (name "Net-(J6-2)") (class "Default")
      (node (ref "J6") (pin "PWM") (pinfunction "2_PWM") (pintype "bidirectional"))
      (node (ref "LED1") (pin "K") (pinfunction "C_K") (pintype "passive"))
      (node (ref "Q3") (pin "2") (pinfunction "D_2") (pintype "passive"))
    )
    (net (code "50") (name "Net-(J6-3)") (class "Default")
      (node (ref "J6") (pin "I/O") (pinfunction "3_I/O") (pintype "bidirectional"))
      (node (ref "R19") (pin "2") (pinfunction "2_2") (pintype "passive"))
    )
    (net (code "51") (name "Net-(LED1-PadA)") (class "Default")
      (node (ref "LED1") (pin "A") (pinfunction "A_A") (pintype "passive"))
      (node (ref "R20") (pin "1") (pinfunction "1_1") (pintype "passive"))
    )
    (net (code "52") (name "Net-(LED2-PadA)") (class "Default")
      (node (ref "LED2") (pin "A") (pinfunction "A_A") (pintype "passive"))
      (node (ref "R25") (pin "1") (pinfunction "1_1") (pintype "passive"))
    )
    (net (code "53") (name "Net-(LED3-PadA)") (class "Default")
      (node (ref "LED3") (pin "A") (pinfunction "A_A") (pintype "passive"))
      (node (ref "R27") (pin "1") (pinfunction "1_1") (pintype "passive"))
    )
    (net (code "54") (name "Net-(LED4-PadA)") (class "Default")
      (node (ref "LED4") (pin "A") (pinfunction "A_A") (pintype "passive"))
      (node (ref "RL4") (pin "2") (pinfunction "2_2") (pintype "passive"))
    )
    (net (code "55") (name "Net-(LED5-PadA)") (class "Default")
      (node (ref "LED5") (pin "A") (pinfunction "A_A") (pintype "passive"))
      (node (ref "R4") (pin "1") (pinfunction "1_1") (pintype "passive"))
    )
    (net (code "56") (name "Net-(LED6-PadA)") (class "Default")
      (node (ref "LED6") (pin "A") (pinfunction "A_A") (pintype "passive"))
      (node (ref "R5") (pin "1") (pinfunction "1_1") (pintype "passive"))
    )
    (net (code "57") (name "Net-(LED7-PadA)") (class "Default")
      (node (ref "LED7") (pin "A") (pinfunction "A_A") (pintype "passive"))
      (node (ref "R6") (pin "1") (pinfunction "1_1") (pintype "passive"))
    )
    (net (code "58") (name "Net-(LED8-PadA)") (class "Default")
      (node (ref "LED8") (pin "A") (pinfunction "A_A") (pintype "passive"))
      (node (ref "R7") (pin "1") (pinfunction "1_1") (pintype "passive"))
    )
    (net (code "59") (name "Net-(LED9-PadA)") (class "Default")
      (node (ref "LED9") (pin "A") (pinfunction "A_A") (pintype "passive"))
      (node (ref "R12") (pin "1") (pinfunction "1_1") (pintype "passive"))
    )
    (net (code "60") (name "Net-(LED11-PadA)") (class "Default")
      (node (ref "LED11") (pin "A") (pinfunction "A_A") (pintype "passive"))
      (node (ref "R14") (pin "1") (pinfunction "1_1") (pintype "passive"))
    )
    (net (code "61") (name "Net-(LED11-PadC)") (class "Default")
      (node (ref "LED11") (pin "C") (pinfunction "C_C") (pintype "passive"))
      (node (ref "U$3") (pin "NET") (pinfunction "NET_NET") (pintype "bidirectional"))
    )
    (net (code "62") (name "Net-(LED12-PadA)") (class "Default")
      (node (ref "LED12") (pin "A") (pinfunction "A_A") (pintype "passive"))
      (node (ref "R39") (pin "1") (pinfunction "1_1") (pintype "passive"))
    )
    (net (code "63") (name "Net-(LED12-PadC)") (class "Default")
      (node (ref "LED12") (pin "C") (pinfunction "C_C") (pintype "passive"))
      (node (ref "U$3") (pin "ALM") (pinfunction "ALM_ALM") (pintype "bidirectional"))
    )
    (net (code "64") (name "Net-(R8-Pad2)") (class "Default")
      (node (ref "R8") (pin "2") (pinfunction "2_2") (pintype "passive"))
      (node (ref "U$3") (pin "TX1") (pinfunction "TX1_TX1") (pintype "bidirectional"))
    )
    (net (code "65") (name "Net-(R11-Pad2)") (class "Default")
      (node (ref "R11") (pin "2") (pinfunction "2_2") (pintype "passive"))
      (node (ref "U$3") (pin "RX1") (pinfunction "RX1_RX1") (pintype "bidirectional"))
    )
    (net (code "66") (name "Net-(R24-Pad2)") (class "Default")
      (node (ref "R24") (pin "2") (pinfunction "2_2") (pintype "passive"))
      (node (ref "X4") (pin "3") (pinfunction "3_3") (pintype "passive"))
    )
    (net (code "67") (name "Net-(R31-Pad2)") (class "Default")
      (node (ref "R31") (pin "2") (pinfunction "2_2") (pintype "passive"))
      (node (ref "X4") (pin "2") (pinfunction "2_2") (pintype "passive"))
    )
    (net (code "68") (name "Net-(U$2-VCORE)") (class "Default")
      (node (ref "C4") (pin "1") (pinfunction "1_1") (pintype "passive"))
      (node (ref "U$2") (pin "1") (pinfunction "VCORE_1") (pintype "bidirectional"))
    )
    (net (code "69") (name "Net-(U$3-RNU)") (class "Default")
      (node (ref "LED9") (pin "C") (pinfunction "C_C") (pintype "passive"))
      (node (ref "U$3") (pin "RUN") (pinfunction "RNU_RUN") (pintype "bidirectional"))
    )
    (net (code "70") (name "Net-(U$4-UCAP)") (class "Default")
      (node (ref "C3") (pin "2") (pinfunction "2_2") (pintype "passive"))
      (node (ref "U$4") (pin "6") (pinfunction "UCAP_6") (pintype "bidirectional"))
    )
    (net (code "71") (name "VCC") (class "Default")
      (node (ref "C10") (pin "1") (pinfunction "1_1") (pintype "passive"))
      (node (ref "C12") (pin "2") (pinfunction "2_2") (pintype "passive"))
      (node (ref "C5") (pin "1") (pinfunction "1_1") (pintype "passive"))
      (node (ref "D2") (pin "C") (pinfunction "C_C") (pintype "passive"))
      (node (ref "D3") (pin "C") (pinfunction "C_C") (pintype "passive"))
      (node (ref "D4") (pin "C") (pinfunction "C_C") (pintype "passive"))
      (node (ref "IC1") (pin "3") (pinfunction "VIN_3") (pintype "input"))
      (node (ref "R15") (pin "2") (pinfunction "2_2") (pintype "passive"))
      (node (ref "RL4") (pin "1") (pinfunction "1_1") (pintype "passive"))
      (node (ref "U$4") (pin "14") (pinfunction "VCC_14") (pintype "bidirectional"))
      (node (ref "U$4") (pin "2") (pinfunction "UVCC_2") (pintype "bidirectional"))
      (node (ref "U$4") (pin "24") (pinfunction "AVCC_24") (pintype "bidirectional"))
      (node (ref "U$4") (pin "34") (pinfunction "VCC1_34") (pintype "bidirectional"))
      (node (ref "U$4") (pin "44") (pinfunction "AVCC1_44") (pintype "bidirectional"))
    )
    (net (code "72") (name "VUSB") (class "Default")
      (node (ref "C7") (pin "2") (pinfunction "2_2") (pintype "passive"))
      (node (ref "D4") (pin "A") (pinfunction "A_A") (pintype "passive"))
      (node (ref "U$4") (pin "7") (pinfunction "VBUS_7") (pintype "bidirectional"))
      (node (ref "X4") (pin "1") (pinfunction "1_1") (pintype "passive"))
    )
    (net (code "73") (name "unconnected-(CFG-Pad2)") (class "Default")
      (node (ref "CFG") (pin "2") (pinfunction "2_2") (pintype "passive"))
    )
    (net (code "74") (name "unconnected-(CFG-Pad3)") (class "Default")
      (node (ref "CFG") (pin "3") (pinfunction "3_3") (pintype "passive"))
    )
    (net (code "75") (name "unconnected-(Q1-D-Pad4)") (class "Default")
      (node (ref "Q1") (pin "4") (pinfunction "D_4") (pintype "passive"))
    )
    (net (code "76") (name "unconnected-(Q2-D-Pad4)") (class "Default")
      (node (ref "Q2") (pin "4") (pinfunction "D_4") (pintype "passive"))
    )
    (net (code "77") (name "unconnected-(Q3-D-Pad4)") (class "Default")
      (node (ref "Q3") (pin "4") (pinfunction "D_4") (pintype "passive"))
    )
    (net (code "78") (name "unconnected-(Q4-D-Pad4)") (class "Default")
      (node (ref "Q4") (pin "4") (pinfunction "D_4") (pintype "passive"))
    )
    (net (code "79") (name "unconnected-(Q5-D-Pad4)") (class "Default")
      (node (ref "Q5") (pin "4") (pinfunction "D_4") (pintype "passive"))
    )
    (net (code "80") (name "unconnected-(Q6-D-Pad4)") (class "Default")
      (node (ref "Q6") (pin "4") (pinfunction "D_4") (pintype "passive"))
    )
    (net (code "81") (name "unconnected-(RESET1-Pad1)") (class "Default")
      (node (ref "RESET1") (pin "1") (pinfunction "1_1") (pintype "passive"))
    )
    (net (code "82") (name "unconnected-(RESET1-Pad3)") (class "Default")
      (node (ref "RESET1") (pin "3") (pinfunction "3_3") (pintype "passive"))
    )
    (net (code "83") (name "unconnected-(U$2-ALARM-Pad4)") (class "Default")
      (node (ref "U$2") (pin "4") (pinfunction "ALARM_4") (pintype "bidirectional"))
    )
    (net (code "84") (name "unconnected-(U$2-PDM_H-Pad6)") (class "Default")
      (node (ref "U$2") (pin "6") (pinfunction "PDM_H_6") (pintype "bidirectional"))
    )
    (net (code "85") (name "unconnected-(U$2-PDM_T-Pad5)") (class "Default")
      (node (ref "U$2") (pin "5") (pinfunction "PDM_T_5") (pintype "bidirectional"))
    )
    (net (code "86") (name "unconnected-(U$3-PadRST)") (class "Default")
      (node (ref "U$3") (pin "RST") (pinfunction "RST_RST") (pintype "bidirectional"))
    )
    (net (code "87") (name "unconnected-(X4-Pad4)") (class "Default")
      (node (ref "X4") (pin "4") (pinfunction "4_4") (pintype "passive"))
    )
  )
)
